# ESC.net
KiCad netlist of a schematic drawn in Altium Designer
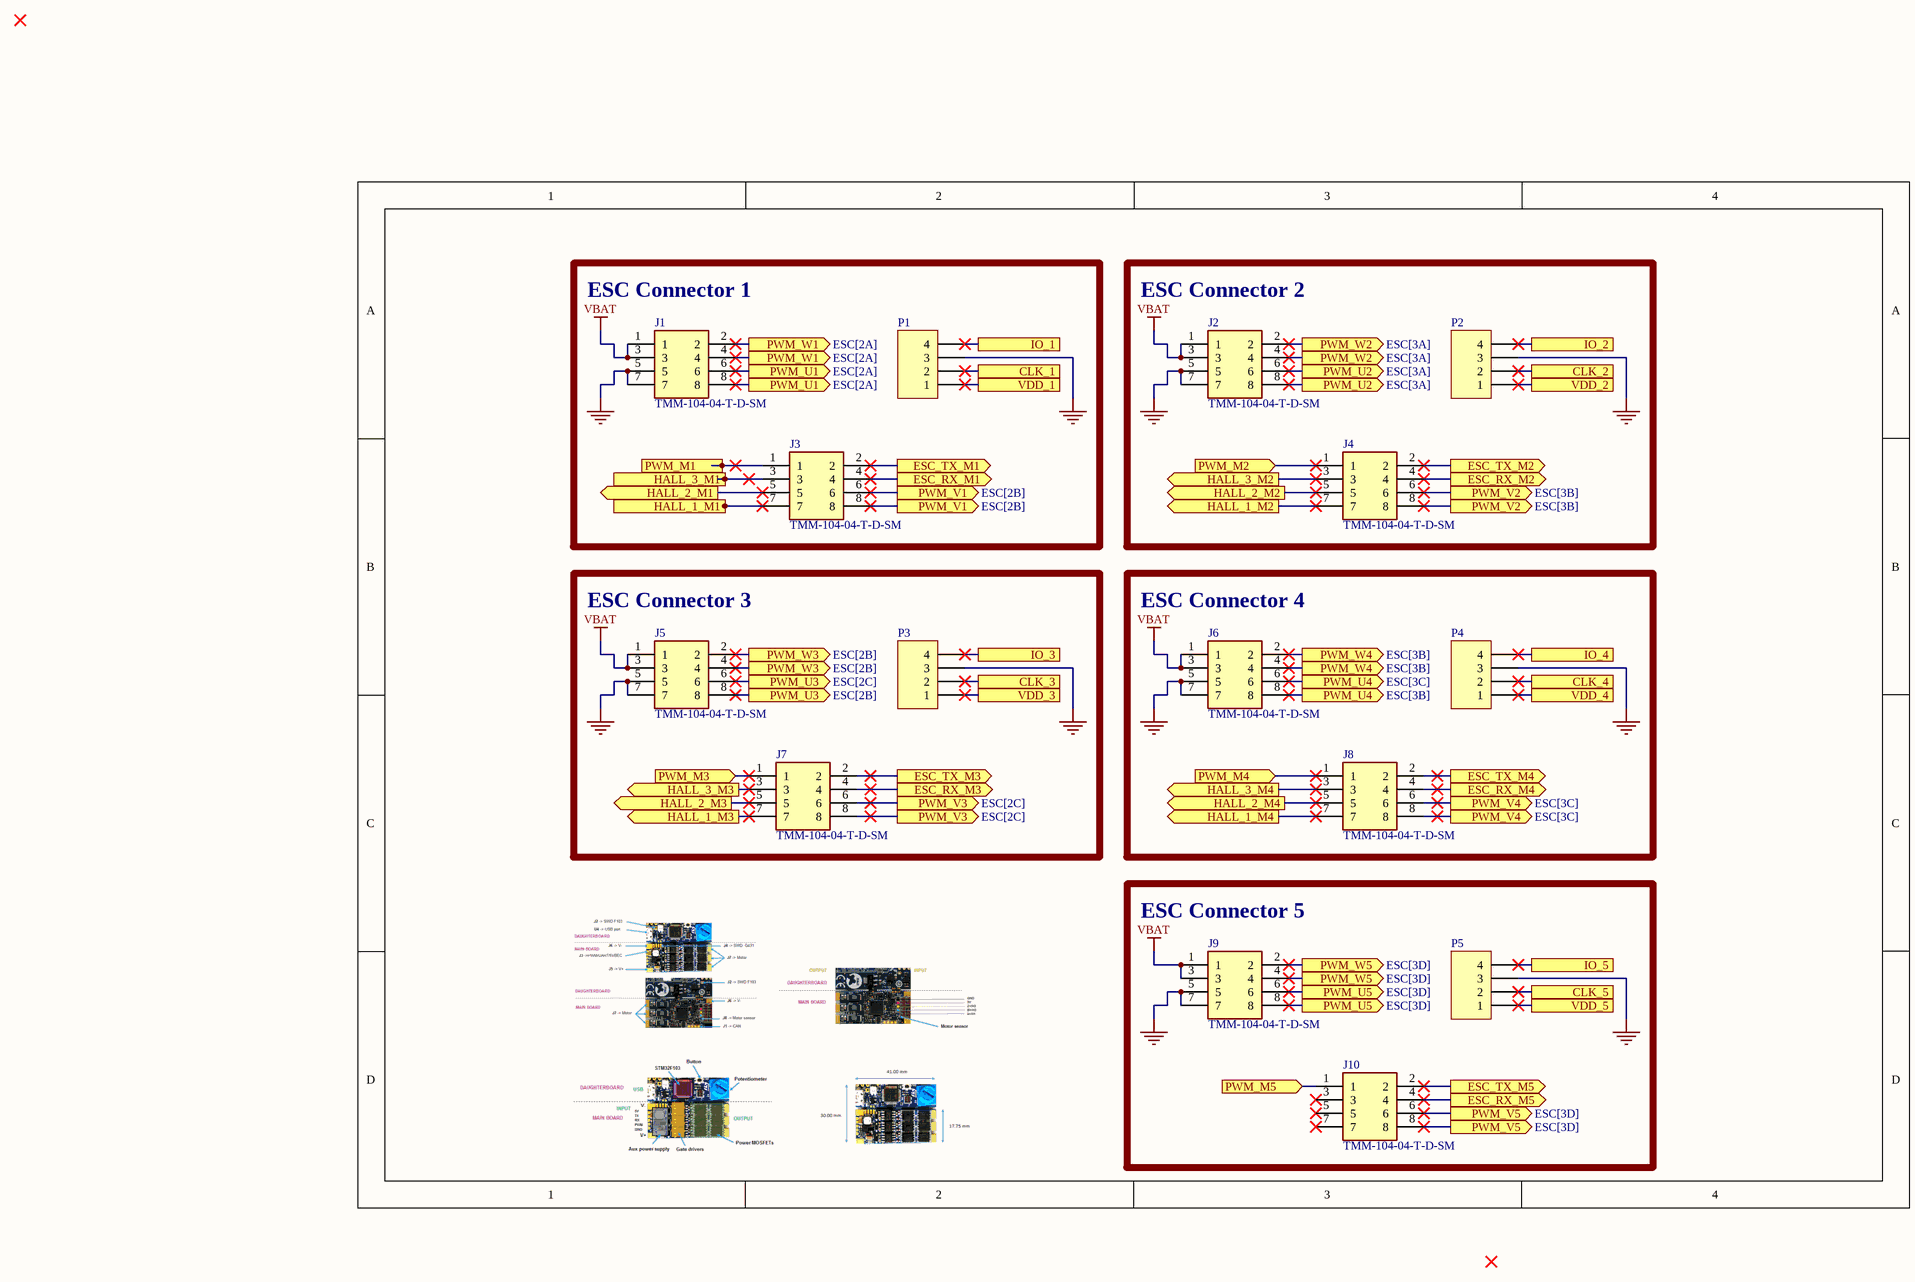
[diagram p0: ESC.SchDoc]

(export (version "E")
  (design (tool "Eeschema 10.0.6"))
  (components
    (comp (ref "J1")
      (value "TMM-104-04-T-D-SM")
      (footprint "roboime:TMM-104-YY-XX-D-SM")
      (description "Connector")
      (libsource (lib "roboime") (part "TMM-104-04-T-D-SM"))
    )
    (comp (ref "J2")
      (value "TMM-104-04-T-D-SM")
      (footprint "roboime:TMM-104-YY-XX-D-SM")
      (description "Connector")
      (libsource (lib "roboime") (part "TMM-104-04-T-D-SM"))
    )
    (comp (ref "J3")
      (value "TMM-104-04-T-D-SM")
      (footprint "roboime:TMM-104-YY-XX-D-SM")
      (description "Connector")
      (libsource (lib "roboime") (part "TMM-104-04-T-D-SM"))
    )
    (comp (ref "J4")
      (value "TMM-104-04-T-D-SM")
      (footprint "roboime:TMM-104-YY-XX-D-SM")
      (description "Connector")
      (libsource (lib "roboime") (part "TMM-104-04-T-D-SM"))
    )
    (comp (ref "J5")
      (value "TMM-104-04-T-D-SM")
      (footprint "roboime:TMM-104-YY-XX-D-SM")
      (description "Connector")
      (libsource (lib "roboime") (part "TMM-104-04-T-D-SM"))
    )
    (comp (ref "J6")
      (value "TMM-104-04-T-D-SM")
      (footprint "roboime:TMM-104-YY-XX-D-SM")
      (description "Connector")
      (libsource (lib "roboime") (part "TMM-104-04-T-D-SM"))
    )
    (comp (ref "J7")
      (value "TMM-104-04-T-D-SM")
      (footprint "roboime:TMM-104-YY-XX-D-SM")
      (description "Connector")
      (libsource (lib "roboime") (part "TMM-104-04-T-D-SM"))
    )
    (comp (ref "J8")
      (value "TMM-104-04-T-D-SM")
      (footprint "roboime:TMM-104-YY-XX-D-SM")
      (description "Connector")
      (libsource (lib "roboime") (part "TMM-104-04-T-D-SM"))
    )
    (comp (ref "J9")
      (value "TMM-104-04-T-D-SM")
      (footprint "roboime:TMM-104-YY-XX-D-SM")
      (description "Connector")
      (libsource (lib "roboime") (part "TMM-104-04-T-D-SM"))
    )
    (comp (ref "J10")
      (value "TMM-104-04-T-D-SM")
      (footprint "roboime:TMM-104-YY-XX-D-SM")
      (description "Connector")
      (libsource (lib "roboime") (part "TMM-104-04-T-D-SM"))
    )
    (comp (ref "P1")
      (value "Header 3")
      (footprint "roboime:My_1X04")
      (description "Header, 4-Pin")
      (fields (field (name "ASID PART NUMBER") "Header 4-AS"))
      (libsource (lib "roboime") (part "Header 4_1"))
    )
    (comp (ref "P2")
      (value "Header 3")
      (footprint "roboime:My_1X04")
      (description "Header, 4-Pin")
      (fields (field (name "ASID PART NUMBER") "Header 4-AS"))
      (libsource (lib "roboime") (part "Header 4_1"))
    )
    (comp (ref "P3")
      (value "Header 3")
      (footprint "roboime:My_1X04")
      (description "Header, 4-Pin")
      (fields (field (name "ASID PART NUMBER") "Header 4-AS"))
      (libsource (lib "roboime") (part "Header 4_1"))
    )
    (comp (ref "P4")
      (value "Header 3")
      (footprint "roboime:My_1X04")
      (description "Header, 4-Pin")
      (fields (field (name "ASID PART NUMBER") "Header 4-AS"))
      (libsource (lib "roboime") (part "Header 4_1"))
    )
    (comp (ref "P5")
      (value "Header 3")
      (footprint "roboime:My_1X04")
      (description "Header, 4-Pin")
      (fields (field (name "ASID PART NUMBER") "Header 4-AS"))
      (libsource (lib "roboime") (part "Header 4_1"))
    )
  )
  (nets
    (net (code "1") (name "/CLK_1") (class "Default")
      (node (ref "P1") (pin "2") (pinfunction "2_2") (pintype "passive+no_connect"))
    )
    (net (code "2") (name "/CLK_2") (class "Default")
      (node (ref "P2") (pin "2") (pinfunction "2_2") (pintype "passive+no_connect"))
    )
    (net (code "3") (name "/CLK_3") (class "Default")
      (node (ref "P3") (pin "2") (pinfunction "2_2") (pintype "passive+no_connect"))
    )
    (net (code "4") (name "/CLK_4") (class "Default")
      (node (ref "P4") (pin "2") (pinfunction "2_2") (pintype "passive+no_connect"))
    )
    (net (code "5") (name "/CLK_5") (class "Default")
      (node (ref "P5") (pin "2") (pinfunction "2_2") (pintype "passive+no_connect"))
    )
    (net (code "6") (name "/ESC_RX_M1") (class "Default")
      (node (ref "J3") (pin "4") (pinfunction "4_4") (pintype "passive+no_connect"))
    )
    (net (code "7") (name "/ESC_RX_M2") (class "Default")
      (node (ref "J4") (pin "4") (pinfunction "4_4") (pintype "passive+no_connect"))
    )
    (net (code "8") (name "/ESC_RX_M3") (class "Default")
      (node (ref "J7") (pin "4") (pinfunction "4_4") (pintype "passive"))
    )
    (net (code "9") (name "/ESC_RX_M4") (class "Default")
      (node (ref "J8") (pin "4") (pinfunction "4_4") (pintype "passive"))
    )
    (net (code "10") (name "/ESC_RX_M5") (class "Default")
      (node (ref "J10") (pin "4") (pinfunction "4_4") (pintype "passive+no_connect"))
    )
    (net (code "11") (name "/ESC_TX_M1") (class "Default")
      (node (ref "J3") (pin "2") (pinfunction "2_2") (pintype "passive+no_connect"))
    )
    (net (code "12") (name "/ESC_TX_M2") (class "Default")
      (node (ref "J4") (pin "2") (pinfunction "2_2") (pintype "passive+no_connect"))
    )
    (net (code "13") (name "/ESC_TX_M3") (class "Default")
      (node (ref "J7") (pin "2") (pinfunction "2_2") (pintype "passive"))
    )
    (net (code "14") (name "/ESC_TX_M4") (class "Default")
      (node (ref "J8") (pin "2") (pinfunction "2_2") (pintype "passive"))
    )
    (net (code "15") (name "/ESC_TX_M5") (class "Default")
      (node (ref "J10") (pin "2") (pinfunction "2_2") (pintype "passive+no_connect"))
    )
    (net (code "16") (name "/HALL_1_M1") (class "Default")
      (node (ref "J3") (pin "7") (pinfunction "7_7") (pintype "passive+no_connect"))
    )
    (net (code "17") (name "/HALL_1_M2") (class "Default")
      (node (ref "J4") (pin "7") (pinfunction "7_7") (pintype "passive+no_connect"))
    )
    (net (code "18") (name "/HALL_1_M3") (class "Default")
      (node (ref "J7") (pin "7") (pinfunction "7_7") (pintype "passive+no_connect"))
    )
    (net (code "19") (name "/HALL_1_M4") (class "Default")
      (node (ref "J8") (pin "7") (pinfunction "7_7") (pintype "passive+no_connect"))
    )
    (net (code "20") (name "/HALL_2_M1") (class "Default")
      (node (ref "J3") (pin "5") (pinfunction "5_5") (pintype "passive+no_connect"))
    )
    (net (code "21") (name "/HALL_2_M2") (class "Default")
      (node (ref "J4") (pin "5") (pinfunction "5_5") (pintype "passive+no_connect"))
    )
    (net (code "22") (name "/HALL_2_M3") (class "Default")
      (node (ref "J7") (pin "5") (pinfunction "5_5") (pintype "passive+no_connect"))
    )
    (net (code "23") (name "/HALL_2_M4") (class "Default")
      (node (ref "J8") (pin "5") (pinfunction "5_5") (pintype "passive+no_connect"))
    )
    (net (code "24") (name "/HALL_3_M1") (class "Default")
      (node (ref "J3") (pin "3") (pinfunction "3_3") (pintype "passive"))
    )
    (net (code "25") (name "/HALL_3_M2") (class "Default")
      (node (ref "J4") (pin "3") (pinfunction "3_3") (pintype "passive+no_connect"))
    )
    (net (code "26") (name "/HALL_3_M3") (class "Default")
      (node (ref "J7") (pin "3") (pinfunction "3_3") (pintype "passive+no_connect"))
    )
    (net (code "27") (name "/HALL_3_M4") (class "Default")
      (node (ref "J8") (pin "3") (pinfunction "3_3") (pintype "passive+no_connect"))
    )
    (net (code "28") (name "/IO_1") (class "Default")
      (node (ref "P1") (pin "4") (pinfunction "4_4") (pintype "passive+no_connect"))
    )
    (net (code "29") (name "/IO_2") (class "Default")
      (node (ref "P2") (pin "4") (pinfunction "4_4") (pintype "passive+no_connect"))
    )
    (net (code "30") (name "/IO_3") (class "Default")
      (node (ref "P3") (pin "4") (pinfunction "4_4") (pintype "passive+no_connect"))
    )
    (net (code "31") (name "/IO_4") (class "Default")
      (node (ref "P4") (pin "4") (pinfunction "4_4") (pintype "passive+no_connect"))
    )
    (net (code "32") (name "/IO_5") (class "Default")
      (node (ref "P5") (pin "4") (pinfunction "4_4") (pintype "passive+no_connect"))
    )
    (net (code "33") (name "/PWM_M1") (class "Default")
      (node (ref "J3") (pin "1") (pinfunction "1_1") (pintype "passive"))
    )
    (net (code "34") (name "/PWM_M2") (class "Default")
      (node (ref "J4") (pin "1") (pinfunction "1_1") (pintype "passive+no_connect"))
    )
    (net (code "35") (name "/PWM_M3") (class "Default")
      (node (ref "J7") (pin "1") (pinfunction "1_1") (pintype "passive+no_connect"))
    )
    (net (code "36") (name "/PWM_M4") (class "Default")
      (node (ref "J8") (pin "1") (pinfunction "1_1") (pintype "passive+no_connect"))
    )
    (net (code "37") (name "/PWM_M5") (class "Default")
      (node (ref "J10") (pin "1") (pinfunction "1_1") (pintype "passive"))
    )
    (net (code "38") (name "/PWM_U1") (class "Default")
      (node (ref "J1") (pin "6") (pinfunction "6_6") (pintype "passive"))
      (node (ref "J1") (pin "8") (pinfunction "8_8") (pintype "passive"))
    )
    (net (code "39") (name "/PWM_U2") (class "Default")
      (node (ref "J2") (pin "6") (pinfunction "6_6") (pintype "passive"))
      (node (ref "J2") (pin "8") (pinfunction "8_8") (pintype "passive"))
    )
    (net (code "40") (name "/PWM_U3") (class "Default")
      (node (ref "J5") (pin "6") (pinfunction "6_6") (pintype "passive"))
      (node (ref "J5") (pin "8") (pinfunction "8_8") (pintype "passive"))
    )
    (net (code "41") (name "/PWM_U4") (class "Default")
      (node (ref "J6") (pin "6") (pinfunction "6_6") (pintype "passive"))
      (node (ref "J6") (pin "8") (pinfunction "8_8") (pintype "passive"))
    )
    (net (code "42") (name "/PWM_U5") (class "Default")
      (node (ref "J9") (pin "6") (pinfunction "6_6") (pintype "passive"))
      (node (ref "J9") (pin "8") (pinfunction "8_8") (pintype "passive"))
    )
    (net (code "43") (name "/PWM_V1") (class "Default")
      (node (ref "J3") (pin "6") (pinfunction "6_6") (pintype "passive"))
      (node (ref "J3") (pin "8") (pinfunction "8_8") (pintype "passive"))
    )
    (net (code "44") (name "/PWM_V2") (class "Default")
      (node (ref "J4") (pin "6") (pinfunction "6_6") (pintype "passive"))
      (node (ref "J4") (pin "8") (pinfunction "8_8") (pintype "passive"))
    )
    (net (code "45") (name "/PWM_V3") (class "Default")
      (node (ref "J7") (pin "6") (pinfunction "6_6") (pintype "passive"))
      (node (ref "J7") (pin "8") (pinfunction "8_8") (pintype "passive"))
    )
    (net (code "46") (name "/PWM_V4") (class "Default")
      (node (ref "J8") (pin "6") (pinfunction "6_6") (pintype "passive"))
      (node (ref "J8") (pin "8") (pinfunction "8_8") (pintype "passive"))
    )
    (net (code "47") (name "/PWM_V5") (class "Default")
      (node (ref "J10") (pin "6") (pinfunction "6_6") (pintype "passive"))
      (node (ref "J10") (pin "8") (pinfunction "8_8") (pintype "passive"))
    )
    (net (code "48") (name "/PWM_W1") (class "Default")
      (node (ref "J1") (pin "2") (pinfunction "2_2") (pintype "passive"))
      (node (ref "J1") (pin "4") (pinfunction "4_4") (pintype "passive"))
    )
    (net (code "49") (name "/PWM_W2") (class "Default")
      (node (ref "J2") (pin "2") (pinfunction "2_2") (pintype "passive"))
      (node (ref "J2") (pin "4") (pinfunction "4_4") (pintype "passive"))
    )
    (net (code "50") (name "/PWM_W3") (class "Default")
      (node (ref "J5") (pin "2") (pinfunction "2_2") (pintype "passive"))
      (node (ref "J5") (pin "4") (pinfunction "4_4") (pintype "passive"))
    )
    (net (code "51") (name "/PWM_W4") (class "Default")
      (node (ref "J6") (pin "2") (pinfunction "2_2") (pintype "passive"))
      (node (ref "J6") (pin "4") (pinfunction "4_4") (pintype "passive"))
    )
    (net (code "52") (name "/PWM_W5") (class "Default")
      (node (ref "J9") (pin "2") (pinfunction "2_2") (pintype "passive"))
      (node (ref "J9") (pin "4") (pinfunction "4_4") (pintype "passive"))
    )
    (net (code "53") (name "/VDD_1") (class "Default")
      (node (ref "P1") (pin "1") (pinfunction "1_1") (pintype "passive+no_connect"))
    )
    (net (code "54") (name "/VDD_2") (class "Default")
      (node (ref "P2") (pin "1") (pinfunction "1_1") (pintype "passive+no_connect"))
    )
    (net (code "55") (name "/VDD_3") (class "Default")
      (node (ref "P3") (pin "1") (pinfunction "1_1") (pintype "passive+no_connect"))
    )
    (net (code "56") (name "/VDD_4") (class "Default")
      (node (ref "P4") (pin "1") (pinfunction "1_1") (pintype "passive+no_connect"))
    )
    (net (code "57") (name "/VDD_5") (class "Default")
      (node (ref "P5") (pin "1") (pinfunction "1_1") (pintype "passive+no_connect"))
    )
    (net (code "58") (name "GND") (class "Default")
      (node (ref "J1") (pin "5") (pinfunction "5_5") (pintype "passive"))
      (node (ref "J1") (pin "7") (pinfunction "7_7") (pintype "passive"))
      (node (ref "J2") (pin "5") (pinfunction "5_5") (pintype "passive"))
      (node (ref "J2") (pin "7") (pinfunction "7_7") (pintype "passive"))
      (node (ref "J5") (pin "5") (pinfunction "5_5") (pintype "passive"))
      (node (ref "J5") (pin "7") (pinfunction "7_7") (pintype "passive"))
      (node (ref "J6") (pin "5") (pinfunction "5_5") (pintype "passive"))
      (node (ref "J6") (pin "7") (pinfunction "7_7") (pintype "passive"))
      (node (ref "J9") (pin "5") (pinfunction "5_5") (pintype "passive"))
      (node (ref "J9") (pin "7") (pinfunction "7_7") (pintype "passive"))
      (node (ref "P1") (pin "3") (pinfunction "3_3") (pintype "passive"))
      (node (ref "P2") (pin "3") (pinfunction "3_3") (pintype "passive"))
      (node (ref "P3") (pin "3") (pinfunction "3_3") (pintype "passive"))
      (node (ref "P4") (pin "3") (pinfunction "3_3") (pintype "passive"))
      (node (ref "P5") (pin "3") (pinfunction "3_3") (pintype "passive"))
    )
    (net (code "59") (name "VBAT") (class "Default")
      (node (ref "J1") (pin "1") (pinfunction "1_1") (pintype "passive"))
      (node (ref "J1") (pin "3") (pinfunction "3_3") (pintype "passive"))
      (node (ref "J2") (pin "1") (pinfunction "1_1") (pintype "passive"))
      (node (ref "J2") (pin "3") (pinfunction "3_3") (pintype "passive"))
      (node (ref "J5") (pin "1") (pinfunction "1_1") (pintype "passive"))
      (node (ref "J5") (pin "3") (pinfunction "3_3") (pintype "passive"))
      (node (ref "J6") (pin "1") (pinfunction "1_1") (pintype "passive"))
      (node (ref "J6") (pin "3") (pinfunction "3_3") (pintype "passive"))
      (node (ref "J9") (pin "1") (pinfunction "1_1") (pintype "passive"))
      (node (ref "J9") (pin "3") (pinfunction "3_3") (pintype "passive"))
    )
    (net (code "60") (name "unconnected-(J10-Pad3)") (class "Default")
      (node (ref "J10") (pin "3") (pinfunction "3_3") (pintype "passive+no_connect"))
    )
    (net (code "61") (name "unconnected-(J10-Pad5)") (class "Default")
      (node (ref "J10") (pin "5") (pinfunction "5_5") (pintype "passive+no_connect"))
    )
    (net (code "62") (name "unconnected-(J10-Pad7)") (class "Default")
      (node (ref "J10") (pin "7") (pinfunction "7_7") (pintype "passive+no_connect"))
    )
  )
)
